# AVALON2_power_21b.net
KiCad netlist of a schematic drawn in Altium Designer
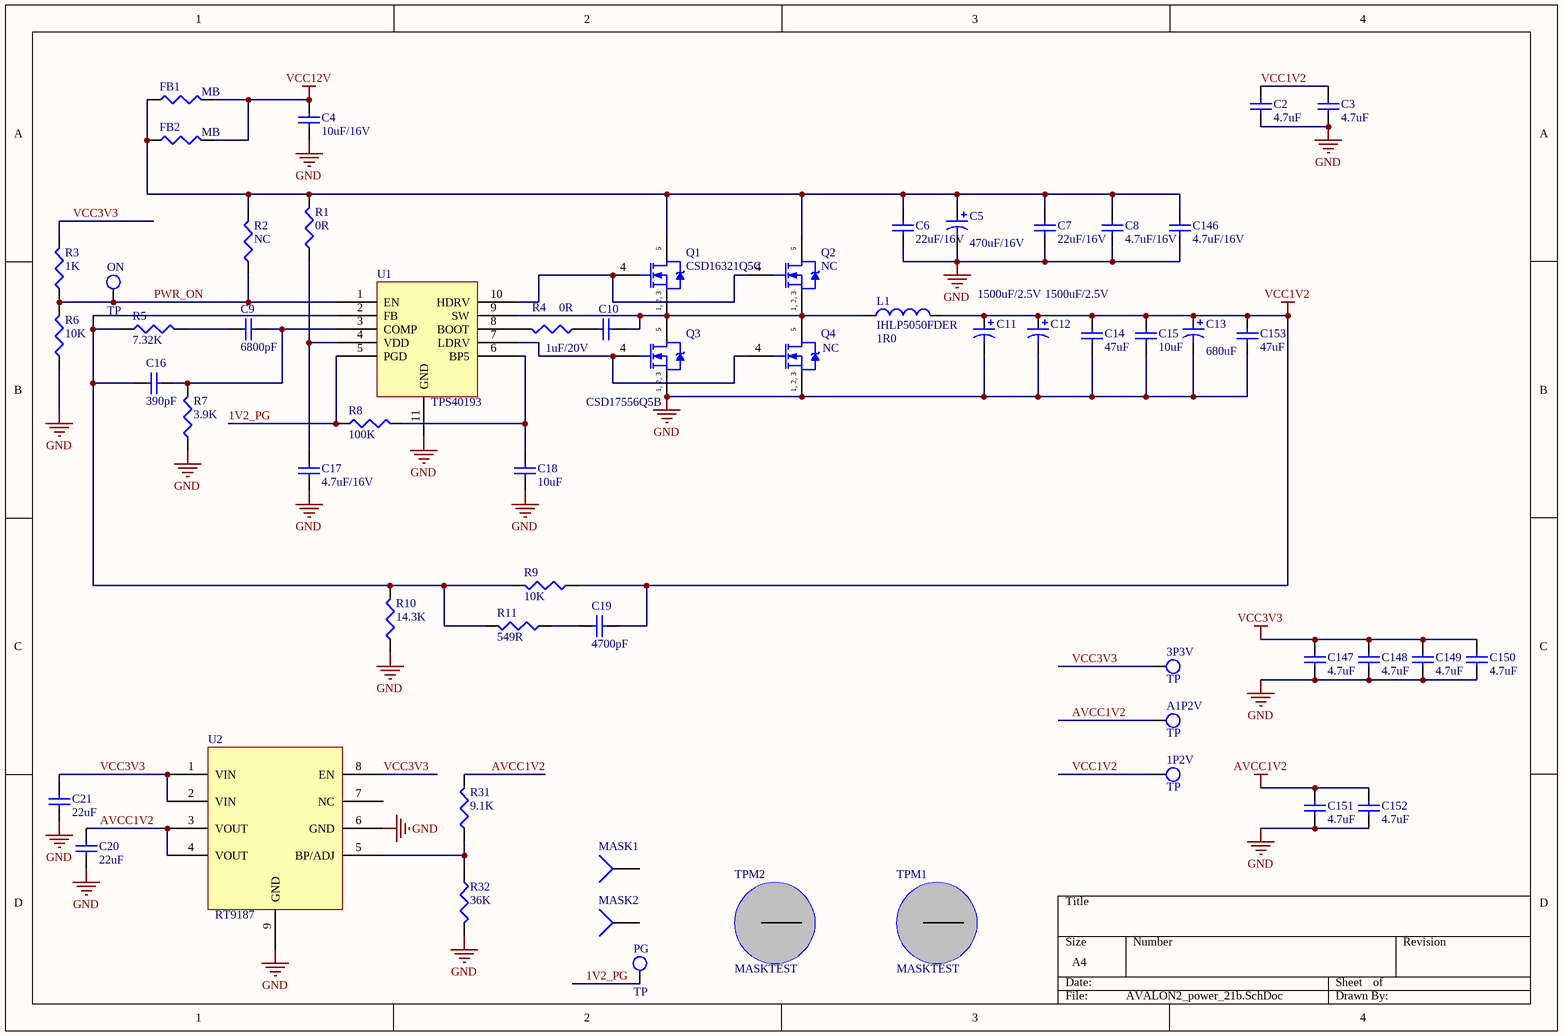
[diagram p0: AVALON2_power_21b.SchDoc]

(export (version "E")
  (design (tool "Eeschema 10.0.6"))
  (components
    (comp (ref "1P2V") (value "TP") (footprint "TP") (libsource (lib "S6") (part "TP")))
    (comp (ref "3P3V") (value "TP") (footprint "TP") (libsource (lib "S6") (part "TP")))
    (comp (ref "A1P2V") (value "TP") (footprint "TP") (libsource (lib "S6") (part "TP")))
    (comp (ref "C2")
      (value "4.7uF")
      (footprint "CAPC1608L")
      (description "Capacitor (Semiconductor SIM Model)")
      (fields (field (name "PUBLISHER") "Altium Limited"))
      (libsource (lib "Miscellaneous Devices") (part "Cap Semi"))
    )
    (comp (ref "C3")
      (value "4.7uF")
      (footprint "CAPC1608L")
      (description "Capacitor (Semiconductor SIM Model)")
      (fields (field (name "PUBLISHER") "Altium Limited"))
      (libsource (lib "Miscellaneous Devices") (part "Cap Semi"))
    )
    (comp (ref "C4")
      (value "10uF/16V")
      (footprint "CAPC3216L")
      (description "Capacitor (Semiconductor SIM Model)")
      (fields (field (name "PUBLISHER") "Altium Limited"))
      (libsource (lib "Miscellaneous Devices") (part "Cap Semi"))
    )
    (comp (ref "C5")
      (value "470uF/16V")
      (footprint "E12")
      (description "Polarized Capacitor (Radial)")
      (fields (field (name "PUBLISHER") "Altium Limited"))
      (libsource (lib "Miscellaneous Devices") (part "Cap Pol1"))
    )
    (comp (ref "C6")
      (value "22uF/16V")
      (footprint "CAPC3225L")
      (description "Capacitor (Semiconductor SIM Model)")
      (fields (field (name "PUBLISHER") "Altium Limited"))
      (libsource (lib "Miscellaneous Devices") (part "Cap Semi"))
    )
    (comp (ref "C7")
      (value "22uF/16V")
      (footprint "CAPC3225L")
      (description "Capacitor (Semiconductor SIM Model)")
      (fields (field (name "PUBLISHER") "Altium Limited"))
      (libsource (lib "Miscellaneous Devices") (part "Cap Semi"))
    )
    (comp (ref "C8")
      (value "4.7uF/16V")
      (footprint "CAPC2012L")
      (description "Capacitor (Semiconductor SIM Model)")
      (fields (field (name "PUBLISHER") "Altium Limited"))
      (libsource (lib "Miscellaneous Devices") (part "Cap Semi"))
    )
    (comp (ref "C9")
      (value "6800pF")
      (footprint "CAPC1608L")
      (description "Capacitor (Semiconductor SIM Model)")
      (fields (field (name "PUBLISHER") "Altium Limited"))
      (libsource (lib "Miscellaneous Devices") (part "Cap Semi"))
    )
    (comp (ref "C10")
      (value "1uF/20V")
      (footprint "CAPC1608L")
      (description "Capacitor (Semiconductor SIM Model)")
      (fields (field (name "PUBLISHER") "Altium Limited"))
      (libsource (lib "Miscellaneous Devices") (part "Cap Semi"))
    )
    (comp (ref "C11")
      (value "1500uF/2.5V")
      (footprint "E12")
      (description "Polarized Capacitor (Radial)")
      (fields (field (name "PUBLISHER") "Altium Limited"))
      (libsource (lib "Miscellaneous Devices") (part "Cap Pol1"))
    )
    (comp (ref "C12")
      (value "1500uF/2.5V")
      (footprint "E12")
      (description "Polarized Capacitor (Radial)")
      (fields (field (name "PUBLISHER") "Altium Limited"))
      (libsource (lib "Miscellaneous Devices") (part "Cap Pol1"))
    )
    (comp (ref "C13")
      (value "680uF")
      (footprint "D")
      (description "Polarized Capacitor (Surface Mount)")
      (fields (field (name "PUBLISHER") "Altium Limited"))
      (libsource (lib "Miscellaneous Devices") (part "Cap Pol3"))
    )
    (comp (ref "C14")
      (value "47uF")
      (footprint "CAPC3225L")
      (description "Capacitor (Semiconductor SIM Model)")
      (fields (field (name "PUBLISHER") "Altium Limited"))
      (libsource (lib "Miscellaneous Devices") (part "Cap Semi"))
    )
    (comp (ref "C15")
      (value "10uF")
      (footprint "CAPC2012L")
      (description "Capacitor (Semiconductor SIM Model)")
      (fields (field (name "PUBLISHER") "Altium Limited"))
      (libsource (lib "Miscellaneous Devices") (part "Cap Semi"))
    )
    (comp (ref "C16")
      (value "390pF")
      (footprint "CAPC1608L")
      (description "Capacitor (Semiconductor SIM Model)")
      (fields (field (name "PUBLISHER") "Altium Limited"))
      (libsource (lib "Miscellaneous Devices") (part "Cap Semi"))
    )
    (comp (ref "C17")
      (value "4.7uF/16V")
      (footprint "CAPC2012L")
      (description "Capacitor (Semiconductor SIM Model)")
      (fields (field (name "PUBLISHER") "Altium Limited"))
      (libsource (lib "Miscellaneous Devices") (part "Cap Semi"))
    )
    (comp (ref "C18")
      (value "10uF")
      (footprint "CAPC2012L")
      (description "Capacitor (Semiconductor SIM Model)")
      (fields (field (name "PUBLISHER") "Altium Limited"))
      (libsource (lib "Miscellaneous Devices") (part "Cap Semi"))
    )
    (comp (ref "C19")
      (value "4700pF")
      (footprint "CAPC1608L")
      (description "Capacitor (Semiconductor SIM Model)")
      (fields (field (name "PUBLISHER") "Altium Limited"))
      (libsource (lib "Miscellaneous Devices") (part "Cap Semi"))
    )
    (comp (ref "C20")
      (value "22uF")
      (footprint "CAPC3216L")
      (description "Capacitor (Semiconductor SIM Model)")
      (fields (field (name "PUBLISHER") "Altium Limited"))
      (libsource (lib "Miscellaneous Devices") (part "Cap Semi"))
    )
    (comp (ref "C21")
      (value "22uF")
      (footprint "CAPC3216L")
      (description "Capacitor (Semiconductor SIM Model)")
      (fields (field (name "PUBLISHER") "Altium Limited"))
      (libsource (lib "Miscellaneous Devices") (part "Cap Semi"))
    )
    (comp (ref "C146")
      (value "4.7uF/16V")
      (footprint "CAPC2012L")
      (description "Capacitor (Semiconductor SIM Model)")
      (fields (field (name "PUBLISHER") "Altium Limited"))
      (libsource (lib "Miscellaneous Devices") (part "Cap Semi"))
    )
    (comp (ref "C147")
      (value "4.7uF")
      (footprint "CAPC1608L")
      (description "Capacitor (Semiconductor SIM Model)")
      (fields (field (name "PUBLISHER") "Altium Limited"))
      (libsource (lib "Miscellaneous Devices") (part "Cap Semi"))
    )
    (comp (ref "C148")
      (value "4.7uF")
      (footprint "CAPC1608L")
      (description "Capacitor (Semiconductor SIM Model)")
      (fields (field (name "PUBLISHER") "Altium Limited"))
      (libsource (lib "Miscellaneous Devices") (part "Cap Semi"))
    )
    (comp (ref "C149")
      (value "4.7uF")
      (footprint "CAPC1608L")
      (description "Capacitor (Semiconductor SIM Model)")
      (fields (field (name "PUBLISHER") "Altium Limited"))
      (libsource (lib "Miscellaneous Devices") (part "Cap Semi"))
    )
    (comp (ref "C150")
      (value "4.7uF")
      (footprint "CAPC1608L")
      (description "Capacitor (Semiconductor SIM Model)")
      (fields (field (name "PUBLISHER") "Altium Limited"))
      (libsource (lib "Miscellaneous Devices") (part "Cap Semi"))
    )
    (comp (ref "C151")
      (value "4.7uF")
      (footprint "CAPC1608L")
      (description "Capacitor (Semiconductor SIM Model)")
      (fields (field (name "PUBLISHER") "Altium Limited"))
      (libsource (lib "Miscellaneous Devices") (part "Cap Semi"))
    )
    (comp (ref "C152")
      (value "4.7uF")
      (footprint "CAPC1608L")
      (description "Capacitor (Semiconductor SIM Model)")
      (fields (field (name "PUBLISHER") "Altium Limited"))
      (libsource (lib "Miscellaneous Devices") (part "Cap Semi"))
    )
    (comp (ref "C153")
      (value "47uF")
      (footprint "CAPC3225L")
      (description "Capacitor (Semiconductor SIM Model)")
      (fields (field (name "PUBLISHER") "Altium Limited"))
      (libsource (lib "Miscellaneous Devices") (part "Cap Semi"))
    )
    (comp (ref "FB1")
      (value "MB")
      (footprint "INDC3216L")
      (description "Resistor")
      (fields (field (name "PUBLISHER") "Altium Limited"))
      (libsource (lib "Miscellaneous Devices") (part "Res3"))
    )
    (comp (ref "FB2")
      (value "MB")
      (footprint "INDC3216L")
      (description "Resistor")
      (fields (field (name "PUBLISHER") "Altium Limited"))
      (libsource (lib "Miscellaneous Devices") (part "Res3"))
    )
    (comp (ref "L1")
      (value "IHLP5050FDER")
      (footprint "IHLP5050")
      (description "Inductor")
      (fields (field (name "ALTIUM_VALUE") "1R0") (field (name "PUBLISHER") "Altium Limited"))
      (libsource (lib "Miscellaneous Devices") (part "Inductor"))
    )
    (comp (ref "MASK1")
      (value "Socket")
      (footprint "MASK_LT")
      (fields (field (name "PUBLISHER") "Altium Limited"))
      (libsource (lib "Miscellaneous Connectors") (part "Socket"))
    )
    (comp (ref "MASK2")
      (value "Socket")
      (footprint "MASK_LT")
      (fields (field (name "PUBLISHER") "Altium Limited"))
      (libsource (lib "Miscellaneous Connectors") (part "Socket"))
    )
    (comp (ref "ON") (value "TP") (footprint "TP") (libsource (lib "S6") (part "TP")))
    (comp (ref "PG") (value "TP") (footprint "TP") (libsource (lib "S6") (part "TP")))
    (comp (ref "Q1") (value "CSD16321Q5C") (footprint "Q5C") (libsource (lib "S6") (part "HAT216X")))
    (comp (ref "Q2") (value "NC") (footprint "Q5C") (libsource (lib "S6") (part "HAT216X")))
    (comp (ref "Q3") (value "CSD17556Q5B") (footprint "Q5B") (libsource (lib "S6") (part "HAT216X")))
    (comp (ref "Q4") (value "NC") (footprint "Q5B") (libsource (lib "S6") (part "HAT216X")))
    (comp (ref "R1")
      (value "0R")
      (footprint "RESC1608L")
      (description "Resistor")
      (fields (field (name "PUBLISHER") "Altium Limited"))
      (libsource (lib "Miscellaneous Devices") (part "Res3"))
    )
    (comp (ref "R2")
      (value "NC")
      (footprint "RESC1005L")
      (description "Resistor")
      (fields (field (name "PUBLISHER") "Altium Limited"))
      (libsource (lib "Miscellaneous Devices") (part "Res3"))
    )
    (comp (ref "R3")
      (value "1K")
      (footprint "RESC1005L")
      (description "Resistor")
      (fields (field (name "PUBLISHER") "Altium Limited"))
      (libsource (lib "Miscellaneous Devices") (part "Res3"))
    )
    (comp (ref "R4")
      (value "0R")
      (footprint "RESC1608L")
      (description "Resistor")
      (fields (field (name "PUBLISHER") "Altium Limited"))
      (libsource (lib "Miscellaneous Devices") (part "Res3"))
    )
    (comp (ref "R5")
      (value "7.32K")
      (footprint "RESC1608L")
      (description "Resistor")
      (fields (field (name "PUBLISHER") "Altium Limited"))
      (libsource (lib "Miscellaneous Devices") (part "Res3"))
    )
    (comp (ref "R6")
      (value "10K")
      (footprint "RESC1608L")
      (description "Resistor")
      (fields (field (name "PUBLISHER") "Altium Limited"))
      (libsource (lib "Miscellaneous Devices") (part "Res3"))
    )
    (comp (ref "R7")
      (value "3.9K")
      (footprint "RESC1608L")
      (description "Resistor")
      (fields (field (name "PUBLISHER") "Altium Limited"))
      (libsource (lib "Miscellaneous Devices") (part "Res3"))
    )
    (comp (ref "R8")
      (value "100K")
      (footprint "RESC1005L")
      (description "Resistor")
      (fields (field (name "PUBLISHER") "Altium Limited"))
      (libsource (lib "Miscellaneous Devices") (part "Res3"))
    )
    (comp (ref "R9")
      (value "10K")
      (footprint "RESC1608L")
      (description "Resistor")
      (fields (field (name "PUBLISHER") "Altium Limited"))
      (libsource (lib "Miscellaneous Devices") (part "Res3"))
    )
    (comp (ref "R10")
      (value "14.3K")
      (footprint "RESC1608L")
      (description "Resistor")
      (fields (field (name "PUBLISHER") "Altium Limited"))
      (libsource (lib "Miscellaneous Devices") (part "Res3"))
    )
    (comp (ref "R11")
      (value "549R")
      (footprint "RESC1608L")
      (description "Resistor")
      (fields (field (name "PUBLISHER") "Altium Limited"))
      (libsource (lib "Miscellaneous Devices") (part "Res3"))
    )
    (comp (ref "R31")
      (value "9.1K")
      (footprint "RESC1608L")
      (description "Resistor")
      (fields (field (name "PUBLISHER") "Altium Limited"))
      (libsource (lib "Miscellaneous Devices") (part "Res3"))
    )
    (comp (ref "R32")
      (value "36K")
      (footprint "RESC1608L")
      (description "Resistor")
      (fields (field (name "PUBLISHER") "Altium Limited"))
      (libsource (lib "Miscellaneous Devices") (part "Res3"))
    )
    (comp (ref "TPM1") (value "MASKTEST") (footprint "MASKTEST") (libsource (lib "S6_2") (part "MASKTEST")))
    (comp (ref "TPM2") (value "MASKTEST") (footprint "MASKTEST") (libsource (lib "S6_2") (part "MASKTEST")))
    (comp (ref "U1") (value "TPS40193") (footprint "SON10") (libsource (lib "S6") (part "TPS40193")))
    (comp (ref "U2")
      (value "RT9187")
      (footprint "DFN-MF8")
      (description "1A, Ultra-Low Dropout, Ultra-Fast CMOS LDO Regulator")
      (libsource (lib "avalon_all") (part "RT9187"))
    )
  )
  (nets
    (net (code "1") (name "/1V2_PG") (class "Default")
      (node (ref "PG") (pin "1") (pinfunction "TP_1") (pintype "passive"))
      (node (ref "R8") (pin "1") (pinfunction "1_1") (pintype "passive"))
      (node (ref "U1") (pin "5") (pinfunction "PGD_5") (pintype "passive"))
    )
    (net (code "2") (name "/PWR_ON") (class "Default")
      (node (ref "ON") (pin "1") (pinfunction "TP_1") (pintype "passive"))
      (node (ref "R2") (pin "1") (pinfunction "1_1") (pintype "passive"))
      (node (ref "R3") (pin "1") (pinfunction "1_1") (pintype "passive"))
      (node (ref "R6") (pin "2") (pinfunction "2_2") (pintype "passive"))
      (node (ref "U1") (pin "1") (pinfunction "EN_1") (pintype "passive"))
    )
    (net (code "3") (name "AVCC1V2") (class "Default")
      (node (ref "A1P2V") (pin "1") (pinfunction "TP_1") (pintype "passive"))
      (node (ref "C151") (pin "2") (pinfunction "2_2") (pintype "passive"))
      (node (ref "C152") (pin "2") (pinfunction "2_2") (pintype "passive"))
      (node (ref "C20") (pin "2") (pinfunction "2_2") (pintype "passive"))
      (node (ref "R31") (pin "2") (pinfunction "2_2") (pintype "passive"))
      (node (ref "U2") (pin "3") (pinfunction "VOUT_3") (pintype "passive"))
      (node (ref "U2") (pin "4") (pinfunction "VOUT_4") (pintype "passive"))
    )
    (net (code "4") (name "GND") (class "Default")
      (node (ref "C11") (pin "2") (pinfunction "2_2") (pintype "passive"))
      (node (ref "C12") (pin "2") (pinfunction "2_2") (pintype "passive"))
      (node (ref "C13") (pin "2") (pinfunction "2_2") (pintype "passive"))
      (node (ref "C14") (pin "1") (pinfunction "1_1") (pintype "passive"))
      (node (ref "C146") (pin "1") (pinfunction "1_1") (pintype "passive"))
      (node (ref "C147") (pin "1") (pinfunction "1_1") (pintype "passive"))
      (node (ref "C148") (pin "1") (pinfunction "1_1") (pintype "passive"))
      (node (ref "C149") (pin "1") (pinfunction "1_1") (pintype "passive"))
      (node (ref "C15") (pin "1") (pinfunction "1_1") (pintype "passive"))
      (node (ref "C150") (pin "1") (pinfunction "1_1") (pintype "passive"))
      (node (ref "C151") (pin "1") (pinfunction "1_1") (pintype "passive"))
      (node (ref "C152") (pin "1") (pinfunction "1_1") (pintype "passive"))
      (node (ref "C153") (pin "1") (pinfunction "1_1") (pintype "passive"))
      (node (ref "C17") (pin "1") (pinfunction "1_1") (pintype "passive"))
      (node (ref "C18") (pin "2") (pinfunction "2_2") (pintype "passive"))
      (node (ref "C2") (pin "1") (pinfunction "1_1") (pintype "passive"))
      (node (ref "C20") (pin "1") (pinfunction "1_1") (pintype "passive"))
      (node (ref "C21") (pin "2") (pinfunction "2_2") (pintype "passive"))
      (node (ref "C3") (pin "1") (pinfunction "1_1") (pintype "passive"))
      (node (ref "C4") (pin "1") (pinfunction "1_1") (pintype "passive"))
      (node (ref "C5") (pin "2") (pinfunction "2_2") (pintype "passive"))
      (node (ref "C6") (pin "1") (pinfunction "1_1") (pintype "passive"))
      (node (ref "C7") (pin "1") (pinfunction "1_1") (pintype "passive"))
      (node (ref "C8") (pin "1") (pinfunction "1_1") (pintype "passive"))
      (node (ref "Q3") (pin "1") (pinfunction "S_1") (pintype "passive"))
      (node (ref "Q3") (pin "2") (pinfunction "S_2") (pintype "passive"))
      (node (ref "Q3") (pin "3") (pinfunction "S_3") (pintype "passive"))
      (node (ref "Q4") (pin "1") (pinfunction "S_1") (pintype "passive"))
      (node (ref "Q4") (pin "2") (pinfunction "S_2") (pintype "passive"))
      (node (ref "Q4") (pin "3") (pinfunction "S_3") (pintype "passive"))
      (node (ref "R10") (pin "1") (pinfunction "1_1") (pintype "passive"))
      (node (ref "R32") (pin "2") (pinfunction "2_2") (pintype "passive"))
      (node (ref "R6") (pin "1") (pinfunction "1_1") (pintype "passive"))
      (node (ref "R7") (pin "1") (pinfunction "1_1") (pintype "passive"))
      (node (ref "U1") (pin "11") (pinfunction "GND_11") (pintype "passive"))
      (node (ref "U2") (pin "6") (pinfunction "GND_6") (pintype "passive"))
      (node (ref "U2") (pin "9") (pinfunction "GND_9") (pintype "passive"))
    )
    (net (code "5") (name "Net-(C9-Pad2)") (class "Default")
      (node (ref "C9") (pin "2") (pinfunction "2_2") (pintype "passive"))
      (node (ref "R5") (pin "2") (pinfunction "2_2") (pintype "passive"))
    )
    (net (code "6") (name "Net-(C10-Pad2)") (class "Default")
      (node (ref "C10") (pin "2") (pinfunction "2_2") (pintype "passive"))
      (node (ref "R4") (pin "1") (pinfunction "1_1") (pintype "passive"))
    )
    (net (code "7") (name "Net-(C19-Pad1)") (class "Default")
      (node (ref "C19") (pin "1") (pinfunction "1_1") (pintype "passive"))
      (node (ref "R11") (pin "1") (pinfunction "1_1") (pintype "passive"))
    )
    (net (code "8") (name "Net-(Q1-D)") (class "Default")
      (node (ref "C146") (pin "2") (pinfunction "2_2") (pintype "passive"))
      (node (ref "C5") (pin "1") (pinfunction "1_1") (pintype "passive"))
      (node (ref "C6") (pin "2") (pinfunction "2_2") (pintype "passive"))
      (node (ref "C7") (pin "2") (pinfunction "2_2") (pintype "passive"))
      (node (ref "C8") (pin "2") (pinfunction "2_2") (pintype "passive"))
      (node (ref "FB1") (pin "1") (pinfunction "1_1") (pintype "passive"))
      (node (ref "FB2") (pin "1") (pinfunction "1_1") (pintype "passive"))
      (node (ref "Q1") (pin "5") (pinfunction "D_5") (pintype "passive"))
      (node (ref "Q2") (pin "5") (pinfunction "D_5") (pintype "passive"))
      (node (ref "R1") (pin "2") (pinfunction "2_2") (pintype "passive"))
      (node (ref "R2") (pin "2") (pinfunction "2_2") (pintype "passive"))
    )
    (net (code "9") (name "Net-(Q1-G)") (class "Default")
      (node (ref "Q1") (pin "4") (pinfunction "G_4") (pintype "passive"))
      (node (ref "Q2") (pin "4") (pinfunction "G_4") (pintype "passive"))
      (node (ref "U1") (pin "10") (pinfunction "HDRV_10") (pintype "passive"))
    )
    (net (code "10") (name "Net-(Q3-D)") (class "Default")
      (node (ref "C10") (pin "1") (pinfunction "1_1") (pintype "passive"))
      (node (ref "L1") (pin "1") (pinfunction "1_1") (pintype "passive"))
      (node (ref "Q1") (pin "1") (pinfunction "S_1") (pintype "passive"))
      (node (ref "Q1") (pin "2") (pinfunction "S_2") (pintype "passive"))
      (node (ref "Q1") (pin "3") (pinfunction "S_3") (pintype "passive"))
      (node (ref "Q2") (pin "1") (pinfunction "S_1") (pintype "passive"))
      (node (ref "Q2") (pin "2") (pinfunction "S_2") (pintype "passive"))
      (node (ref "Q2") (pin "3") (pinfunction "S_3") (pintype "passive"))
      (node (ref "Q3") (pin "5") (pinfunction "D_5") (pintype "passive"))
      (node (ref "Q4") (pin "5") (pinfunction "D_5") (pintype "passive"))
      (node (ref "U1") (pin "9") (pinfunction "SW_9") (pintype "passive"))
    )
    (net (code "11") (name "Net-(Q3-G)") (class "Default")
      (node (ref "Q3") (pin "4") (pinfunction "G_4") (pintype "passive"))
      (node (ref "Q4") (pin "4") (pinfunction "G_4") (pintype "passive"))
      (node (ref "U1") (pin "7") (pinfunction "LDRV_7") (pintype "passive"))
    )
    (net (code "12") (name "Net-(U1-BOOT)") (class "Default")
      (node (ref "R4") (pin "2") (pinfunction "2_2") (pintype "passive"))
      (node (ref "U1") (pin "8") (pinfunction "BOOT_8") (pintype "passive"))
    )
    (net (code "13") (name "Net-(U1-BP5)") (class "Default")
      (node (ref "C18") (pin "1") (pinfunction "1_1") (pintype "passive"))
      (node (ref "R8") (pin "2") (pinfunction "2_2") (pintype "passive"))
      (node (ref "U1") (pin "6") (pinfunction "BP5_6") (pintype "passive"))
    )
    (net (code "14") (name "Net-(U1-COMP)") (class "Default")
      (node (ref "C16") (pin "1") (pinfunction "1_1") (pintype "passive"))
      (node (ref "C9") (pin "1") (pinfunction "1_1") (pintype "passive"))
      (node (ref "R7") (pin "2") (pinfunction "2_2") (pintype "passive"))
      (node (ref "U1") (pin "3") (pinfunction "COMP_3") (pintype "passive"))
    )
    (net (code "15") (name "Net-(U1-FB)") (class "Default")
      (node (ref "C16") (pin "2") (pinfunction "2_2") (pintype "passive"))
      (node (ref "R10") (pin "2") (pinfunction "2_2") (pintype "passive"))
      (node (ref "R11") (pin "2") (pinfunction "2_2") (pintype "passive"))
      (node (ref "R5") (pin "1") (pinfunction "1_1") (pintype "passive"))
      (node (ref "R9") (pin "2") (pinfunction "2_2") (pintype "passive"))
      (node (ref "U1") (pin "2") (pinfunction "FB_2") (pintype "passive"))
    )
    (net (code "16") (name "Net-(U1-VDD)") (class "Default")
      (node (ref "C17") (pin "2") (pinfunction "2_2") (pintype "passive"))
      (node (ref "R1") (pin "1") (pinfunction "1_1") (pintype "passive"))
      (node (ref "U1") (pin "4") (pinfunction "VDD_4") (pintype "passive"))
    )
    (net (code "17") (name "Net-(U2-BP{slash}ADJ)") (class "Default")
      (node (ref "R31") (pin "1") (pinfunction "1_1") (pintype "passive"))
      (node (ref "R32") (pin "1") (pinfunction "1_1") (pintype "passive"))
      (node (ref "U2") (pin "5") (pinfunction "BP/ADJ_5") (pintype "passive"))
    )
    (net (code "18") (name "VCC1V2") (class "Default")
      (node (ref "1P2V") (pin "1") (pinfunction "TP_1") (pintype "passive"))
      (node (ref "C11") (pin "1") (pinfunction "1_1") (pintype "passive"))
      (node (ref "C12") (pin "1") (pinfunction "1_1") (pintype "passive"))
      (node (ref "C13") (pin "1") (pinfunction "1_1") (pintype "passive"))
      (node (ref "C14") (pin "2") (pinfunction "2_2") (pintype "passive"))
      (node (ref "C15") (pin "2") (pinfunction "2_2") (pintype "passive"))
      (node (ref "C153") (pin "2") (pinfunction "2_2") (pintype "passive"))
      (node (ref "C19") (pin "2") (pinfunction "2_2") (pintype "passive"))
      (node (ref "C2") (pin "2") (pinfunction "2_2") (pintype "passive"))
      (node (ref "C3") (pin "2") (pinfunction "2_2") (pintype "passive"))
      (node (ref "L1") (pin "2") (pinfunction "2_2") (pintype "passive"))
      (node (ref "R9") (pin "1") (pinfunction "1_1") (pintype "passive"))
    )
    (net (code "19") (name "VCC3V3") (class "Default")
      (node (ref "3P3V") (pin "1") (pinfunction "TP_1") (pintype "passive"))
      (node (ref "C147") (pin "2") (pinfunction "2_2") (pintype "passive"))
      (node (ref "C148") (pin "2") (pinfunction "2_2") (pintype "passive"))
      (node (ref "C149") (pin "2") (pinfunction "2_2") (pintype "passive"))
      (node (ref "C150") (pin "2") (pinfunction "2_2") (pintype "passive"))
      (node (ref "C21") (pin "1") (pinfunction "1_1") (pintype "passive"))
      (node (ref "R3") (pin "2") (pinfunction "2_2") (pintype "passive"))
      (node (ref "U2") (pin "1") (pinfunction "VIN_1") (pintype "passive"))
      (node (ref "U2") (pin "2") (pinfunction "VIN_2") (pintype "passive"))
      (node (ref "U2") (pin "8") (pinfunction "EN_8") (pintype "passive"))
    )
    (net (code "20") (name "VCC12V") (class "Default")
      (node (ref "C4") (pin "2") (pinfunction "2_2") (pintype "passive"))
      (node (ref "FB1") (pin "2") (pinfunction "2_2") (pintype "passive"))
      (node (ref "FB2") (pin "2") (pinfunction "2_2") (pintype "passive"))
    )
    (net (code "21") (name "unconnected-(MASK1-Pad1)") (class "Default")
      (node (ref "MASK1") (pin "1") (pinfunction "1_1") (pintype "passive"))
    )
    (net (code "22") (name "unconnected-(MASK2-Pad1)") (class "Default")
      (node (ref "MASK2") (pin "1") (pinfunction "1_1") (pintype "passive"))
    )
    (net (code "23") (name "unconnected-(TPM1-MASKTEST-Pad0)") (class "Default")
      (node (ref "TPM1") (pin "0") (pinfunction "MASKTEST_0") (pintype "passive"))
    )
    (net (code "24") (name "unconnected-(TPM2-MASKTEST-Pad0)") (class "Default")
      (node (ref "TPM2") (pin "0") (pinfunction "MASKTEST_0") (pintype "passive"))
    )
    (net (code "25") (name "unconnected-(U2-NC-Pad7)") (class "Default")
      (node (ref "U2") (pin "7") (pinfunction "NC_7") (pintype "passive"))
    )
  )
)
